# MRCS-BB-Wemos.net
KiCad netlist of a schematic drawn in EAGLE
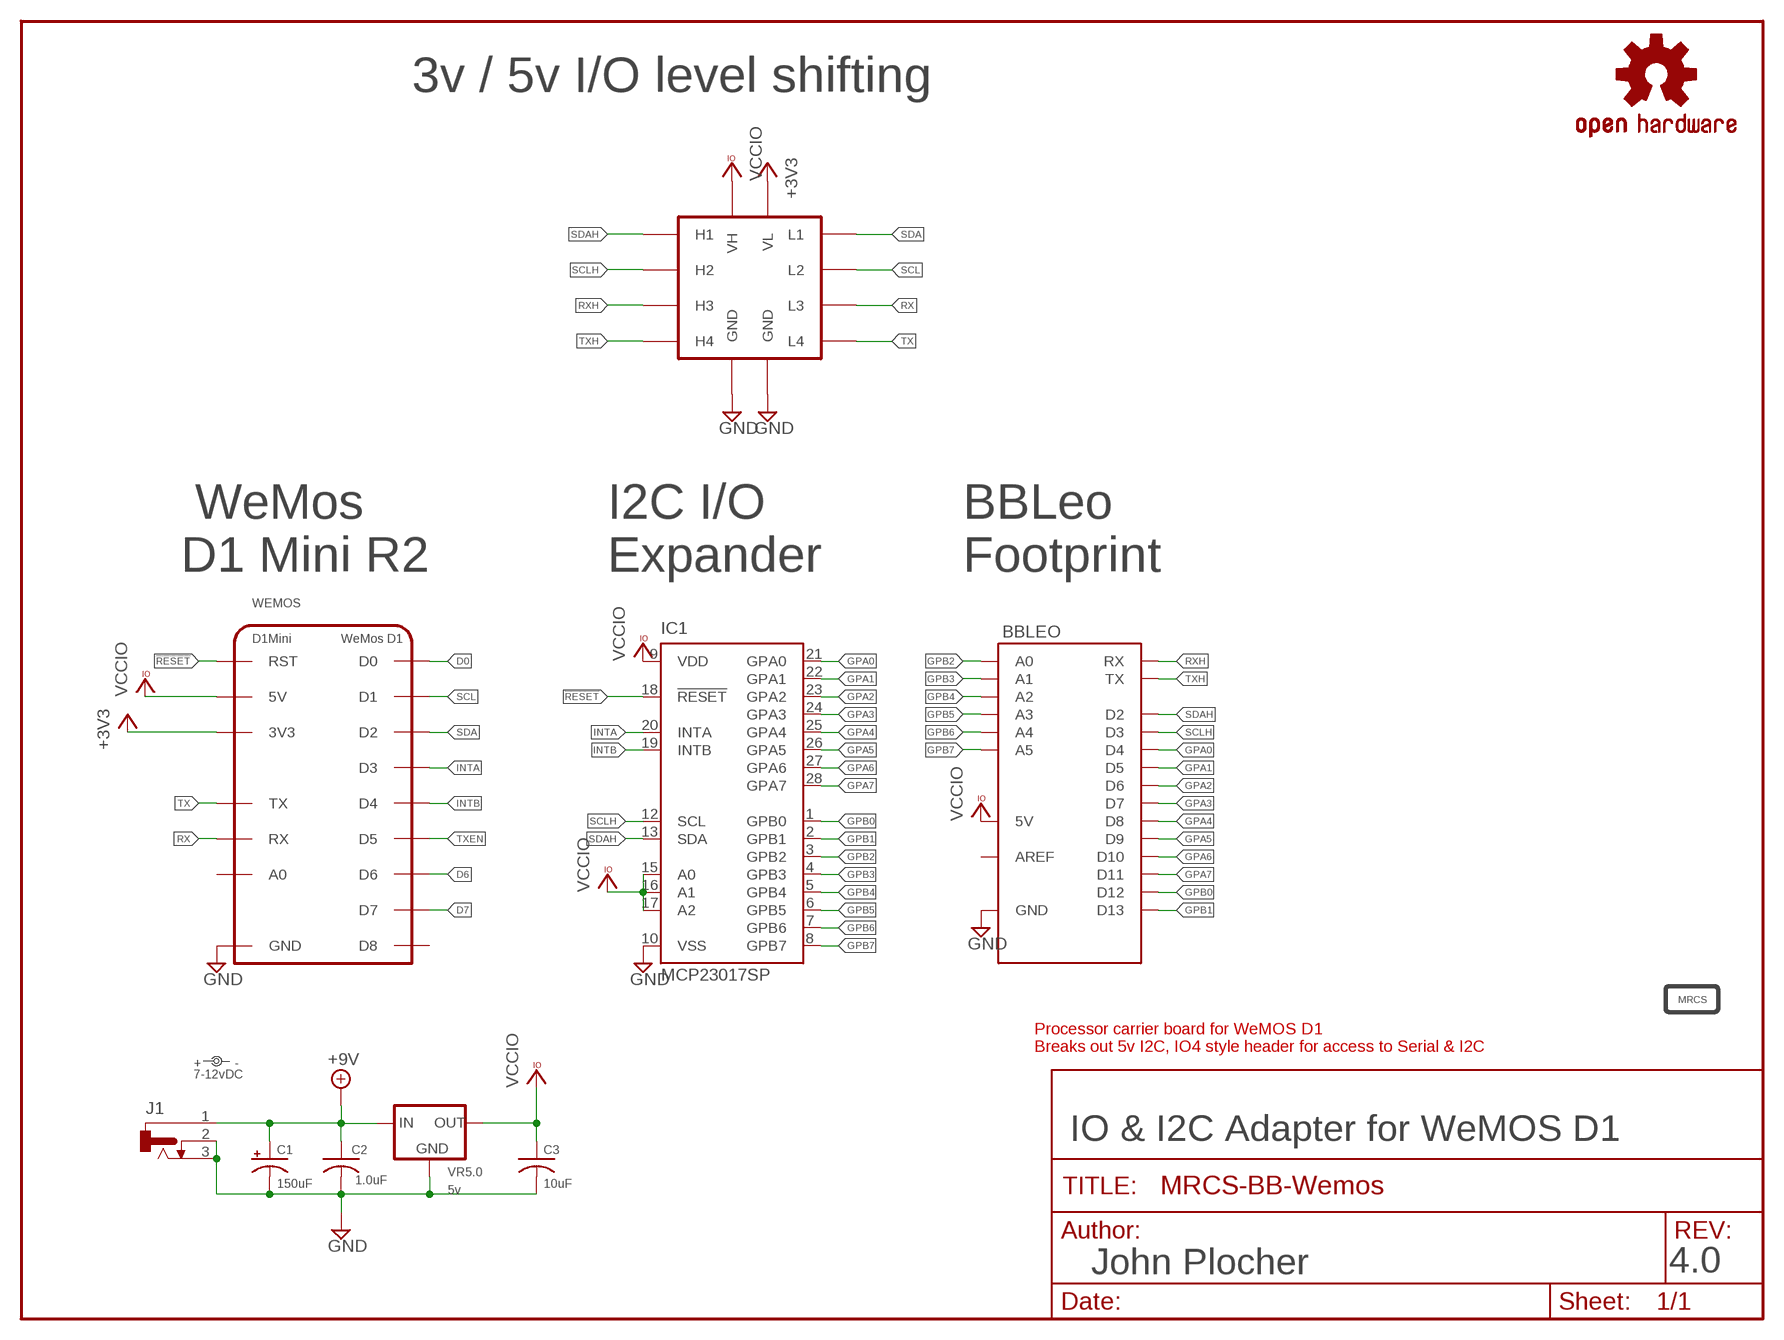
[diagram p0: schematic, sheet 1]

(export (version "E")
  (design (tool "Eeschema 10.0.6"))
  (components
    (comp (ref "BBLEO")
      (value "ARDUINO-BBLEO")
      (footprint "eagle-import:ARDUINO-BBLEO")
      (libsource (lib "eagle-import") (part "ARDUINO-BBLEO"))
    )
    (comp (ref "C1")
      (value "150uF")
      (footprint "eagle-import:E5-10.5")
      (libsource (lib "eagle-import") (part "CAP-POLPTH-5MM"))
    )
    (comp (ref "C2")
      (value "1.0uF")
      (footprint "eagle-import:C050-024X044")
      (libsource (lib "eagle-import") (part "CAPPTH1"))
    )
    (comp (ref "C3")
      (value "10uF")
      (footprint "eagle-import:C050-024X044")
      (libsource (lib "eagle-import") (part "CAPPTH1"))
    )
    (comp (ref "IC1")
      (value "MCP23017SP")
      (footprint "eagle-import:DIL28-3")
      (fields (field (name "MF") "MICROCHIP") (field (name "MPN") "MCP23017-E/SP"))
      (libsource (lib "eagle-import") (part "MCP23017SP"))
    )
    (comp (ref "J1")
      (value "CONNECTOR-DC-POWER-RA")
      (footprint "eagle-import:DCJ0202")
      (libsource (lib "eagle-import") (part "CONNECTOR-DC-POWER-RA"))
    )
    (comp (ref "LABEL1")
      (value "7-12vDC")
      (footprint "eagle-import:PWR_LABEL")
      (libsource (lib "eagle-import") (part "DOC-POWER_LABEL"))
    )
    (comp (ref "LS2")
      (value "I2C-LEVELSHIFTER")
      (footprint "eagle-import:MODULE")
      (libsource (lib "eagle-import") (part "I2C-LEVELSHIFTER"))
    )
    (comp (ref "OSHW1")
      (value "DOC-OSHW-LOGO-L")
      (footprint "eagle-import:OSHW-LOGO-L")
      (libsource (lib "eagle-import") (part "DOC-OSHW-LOGO-L"))
    )
    (comp (ref "U$1")
      (value "DOC-MRCS-LOGOTOP")
      (footprint "eagle-import:MRCS-LOGO")
      (libsource (lib "eagle-import") (part "DOC-MRCS-LOGOTOP"))
    )
    (comp (ref "VR5.0")
      (value "5v")
      (footprint "eagle-import:TO-220-RA")
      (libsource (lib "eagle-import") (part "VREG-?-PTH-RA"))
    )
    (comp (ref "WEMOS")
      (value "D1Mini")
      (footprint "eagle-import:WEMOS-D1")
      (libsource (lib "eagle-import") (part "WEMOS-D1V1"))
    )
  )
  (nets
    (net (code "1") (name "+3V3") (class "Default")
      (node (ref "LS2") (pin "LV") (pinfunction "VL_LV") (pintype "bidirectional"))
      (node (ref "WEMOS") (pin "3V3") (pinfunction "3V3_3V3") (pintype "bidirectional"))
    )
    (net (code "2") (name "+9V") (class "Default")
      (node (ref "C1") (pin "+") (pinfunction "+_+") (pintype "passive"))
      (node (ref "C2") (pin "1") (pinfunction "1_1") (pintype "passive"))
      (node (ref "J1") (pin "1") (pinfunction "1_1") (pintype "passive"))
      (node (ref "VR5.0") (pin "IN") (pinfunction "IN_IN") (pintype "input"))
    )
    (net (code "3") (name "/~{RESET}") (class "Default")
      (node (ref "IC1") (pin "18") (pinfunction "~{RESET}_18") (pintype "input"))
      (node (ref "WEMOS") (pin "RST") (pinfunction "RST_RST") (pintype "bidirectional"))
    )
    (net (code "4") (name "D0") (class "Default")
      (node (ref "WEMOS") (pin "D0") (pinfunction "D0_D0") (pintype "bidirectional"))
    )
    (net (code "5") (name "D6") (class "Default")
      (node (ref "WEMOS") (pin "D6") (pinfunction "D6_D6") (pintype "bidirectional"))
    )
    (net (code "6") (name "D7") (class "Default")
      (node (ref "WEMOS") (pin "D7") (pinfunction "D7_D7") (pintype "bidirectional"))
    )
    (net (code "7") (name "GND") (class "Default")
      (node (ref "BBLEO") (pin "GND@0") (pinfunction "GND_GND@0") (pintype "bidirectional"))
      (node (ref "BBLEO") (pin "GND@1") (pinfunction "GND_GND@1") (pintype "bidirectional"))
      (node (ref "BBLEO") (pin "GND@2") (pinfunction "GND_GND@2") (pintype "bidirectional"))
      (node (ref "BBLEO") (pin "GND@3") (pinfunction "GND_GND@3") (pintype "bidirectional"))
      (node (ref "BBLEO") (pin "GND@4") (pinfunction "GND_GND@4") (pintype "bidirectional"))
      (node (ref "C1") (pin "-") (pinfunction "-_-") (pintype "passive"))
      (node (ref "C2") (pin "2") (pinfunction "2_2") (pintype "passive"))
      (node (ref "C3") (pin "2") (pinfunction "2_2") (pintype "passive"))
      (node (ref "IC1") (pin "10") (pinfunction "VSS_10") (pintype "power_in"))
      (node (ref "J1") (pin "2") (pinfunction "2_2") (pintype "passive"))
      (node (ref "J1") (pin "3") (pinfunction "3_3") (pintype "passive"))
      (node (ref "LS2") (pin "GND@0") (pinfunction "GND_GND@0") (pintype "bidirectional"))
      (node (ref "LS2") (pin "GND@1") (pinfunction "GND_GND@1") (pintype "bidirectional"))
      (node (ref "VR5.0") (pin "GND") (pinfunction "GND_GND") (pintype "input"))
      (node (ref "WEMOS") (pin "GND") (pinfunction "GND_GND") (pintype "bidirectional"))
    )
    (net (code "8") (name "GPA0") (class "Default")
      (node (ref "BBLEO") (pin "D4") (pinfunction "D4_D4") (pintype "bidirectional"))
      (node (ref "IC1") (pin "21") (pinfunction "GPA0_21") (pintype "bidirectional"))
    )
    (net (code "9") (name "GPA1") (class "Default")
      (node (ref "BBLEO") (pin "D5") (pinfunction "D5_D5") (pintype "bidirectional"))
      (node (ref "IC1") (pin "22") (pinfunction "GPA1_22") (pintype "bidirectional"))
    )
    (net (code "10") (name "GPA2") (class "Default")
      (node (ref "BBLEO") (pin "D6") (pinfunction "D6_D6") (pintype "bidirectional"))
      (node (ref "IC1") (pin "23") (pinfunction "GPA2_23") (pintype "bidirectional"))
    )
    (net (code "11") (name "GPA3") (class "Default")
      (node (ref "BBLEO") (pin "D7") (pinfunction "D7_D7") (pintype "bidirectional"))
      (node (ref "IC1") (pin "24") (pinfunction "GPA3_24") (pintype "bidirectional"))
    )
    (net (code "12") (name "GPA4") (class "Default")
      (node (ref "BBLEO") (pin "D8") (pinfunction "D8_D8") (pintype "bidirectional"))
      (node (ref "IC1") (pin "25") (pinfunction "GPA4_25") (pintype "bidirectional"))
    )
    (net (code "13") (name "GPA5") (class "Default")
      (node (ref "BBLEO") (pin "D9") (pinfunction "D9_D9") (pintype "bidirectional"))
      (node (ref "IC1") (pin "26") (pinfunction "GPA5_26") (pintype "bidirectional"))
    )
    (net (code "14") (name "GPA6") (class "Default")
      (node (ref "BBLEO") (pin "D10") (pinfunction "D10_D10") (pintype "bidirectional"))
      (node (ref "IC1") (pin "27") (pinfunction "GPA6_27") (pintype "bidirectional"))
    )
    (net (code "15") (name "GPA7") (class "Default")
      (node (ref "BBLEO") (pin "D11") (pinfunction "D11_D11") (pintype "bidirectional"))
      (node (ref "IC1") (pin "28") (pinfunction "GPA7_28") (pintype "bidirectional"))
    )
    (net (code "16") (name "GPB0") (class "Default")
      (node (ref "BBLEO") (pin "D12") (pinfunction "D12_D12") (pintype "bidirectional"))
      (node (ref "IC1") (pin "1") (pinfunction "GPB0_1") (pintype "bidirectional"))
    )
    (net (code "17") (name "GPB1") (class "Default")
      (node (ref "BBLEO") (pin "D13") (pinfunction "D13_D13") (pintype "bidirectional"))
      (node (ref "IC1") (pin "2") (pinfunction "GPB1_2") (pintype "bidirectional"))
    )
    (net (code "18") (name "GPB2") (class "Default")
      (node (ref "BBLEO") (pin "A0") (pinfunction "A0_A0") (pintype "bidirectional"))
      (node (ref "IC1") (pin "3") (pinfunction "GPB2_3") (pintype "bidirectional"))
    )
    (net (code "19") (name "GPB3") (class "Default")
      (node (ref "BBLEO") (pin "A1") (pinfunction "A1_A1") (pintype "bidirectional"))
      (node (ref "IC1") (pin "4") (pinfunction "GPB3_4") (pintype "bidirectional"))
    )
    (net (code "20") (name "GPB4") (class "Default")
      (node (ref "BBLEO") (pin "A2") (pinfunction "A2_A2") (pintype "bidirectional"))
      (node (ref "IC1") (pin "5") (pinfunction "GPB4_5") (pintype "bidirectional"))
    )
    (net (code "21") (name "GPB5") (class "Default")
      (node (ref "BBLEO") (pin "A3") (pinfunction "A3_A3") (pintype "bidirectional"))
      (node (ref "IC1") (pin "6") (pinfunction "GPB5_6") (pintype "bidirectional"))
    )
    (net (code "22") (name "GPB6") (class "Default")
      (node (ref "BBLEO") (pin "A4") (pinfunction "A4_A4") (pintype "bidirectional"))
      (node (ref "IC1") (pin "7") (pinfunction "GPB6_7") (pintype "bidirectional"))
    )
    (net (code "23") (name "GPB7") (class "Default")
      (node (ref "BBLEO") (pin "A5") (pinfunction "A5_A5") (pintype "bidirectional"))
      (node (ref "IC1") (pin "8") (pinfunction "GPB7_8") (pintype "bidirectional"))
    )
    (net (code "24") (name "INTA") (class "Default")
      (node (ref "IC1") (pin "20") (pinfunction "INTA_20") (pintype "output"))
      (node (ref "WEMOS") (pin "D3") (pinfunction "D3_D3") (pintype "bidirectional"))
    )
    (net (code "25") (name "INTB") (class "Default")
      (node (ref "IC1") (pin "19") (pinfunction "INTB_19") (pintype "output"))
      (node (ref "WEMOS") (pin "D4") (pinfunction "D4_D4") (pintype "bidirectional"))
    )
    (net (code "26") (name "RX") (class "Default")
      (node (ref "LS2") (pin "L3") (pinfunction "L3_L3") (pintype "bidirectional"))
      (node (ref "WEMOS") (pin "RX") (pinfunction "RX_RX") (pintype "bidirectional"))
    )
    (net (code "27") (name "RXH") (class "Default")
      (node (ref "BBLEO") (pin "RX") (pinfunction "RX_RX") (pintype "bidirectional"))
      (node (ref "LS2") (pin "H3") (pinfunction "H3_H3") (pintype "bidirectional"))
    )
    (net (code "28") (name "SCL") (class "Default")
      (node (ref "LS2") (pin "L2") (pinfunction "L2_L2") (pintype "bidirectional"))
      (node (ref "WEMOS") (pin "D1") (pinfunction "D1_D1") (pintype "bidirectional"))
    )
    (net (code "29") (name "SCLH") (class "Default")
      (node (ref "BBLEO") (pin "SCL") (pinfunction "D3_SCL") (pintype "bidirectional"))
      (node (ref "IC1") (pin "12") (pinfunction "SCL_12") (pintype "input"))
      (node (ref "LS2") (pin "H2") (pinfunction "H2_H2") (pintype "bidirectional"))
    )
    (net (code "30") (name "SDA") (class "Default")
      (node (ref "LS2") (pin "L1") (pinfunction "L1_L1") (pintype "bidirectional"))
      (node (ref "WEMOS") (pin "D2") (pinfunction "D2_D2") (pintype "bidirectional"))
    )
    (net (code "31") (name "SDAH") (class "Default")
      (node (ref "BBLEO") (pin "SDA") (pinfunction "D2_SDA") (pintype "bidirectional"))
      (node (ref "IC1") (pin "13") (pinfunction "SDA_13") (pintype "bidirectional"))
      (node (ref "LS2") (pin "H1") (pinfunction "H1_H1") (pintype "bidirectional"))
    )
    (net (code "32") (name "TX") (class "Default")
      (node (ref "LS2") (pin "L4") (pinfunction "L4_L4") (pintype "bidirectional"))
      (node (ref "WEMOS") (pin "TX") (pinfunction "TX_TX") (pintype "bidirectional"))
    )
    (net (code "33") (name "TXEN") (class "Default")
      (node (ref "WEMOS") (pin "D5") (pinfunction "D5_D5") (pintype "bidirectional"))
    )
    (net (code "34") (name "TXH") (class "Default")
      (node (ref "BBLEO") (pin "TX") (pinfunction "TX_TX") (pintype "bidirectional"))
      (node (ref "LS2") (pin "H4") (pinfunction "H4_H4") (pintype "bidirectional"))
    )
    (net (code "35") (name "VCCIO") (class "Default")
      (node (ref "BBLEO") (pin "+5V@1") (pinfunction "5V_+5V@1") (pintype "bidirectional"))
      (node (ref "BBLEO") (pin "+5V@2") (pinfunction "5V_+5V@2") (pintype "bidirectional"))
      (node (ref "BBLEO") (pin "+5V@3") (pinfunction "5V_+5V@3") (pintype "bidirectional"))
      (node (ref "BBLEO") (pin "+5V@4") (pinfunction "5V_+5V@4") (pintype "bidirectional"))
      (node (ref "C3") (pin "1") (pinfunction "1_1") (pintype "passive"))
      (node (ref "IC1") (pin "15") (pinfunction "A0_15") (pintype "input"))
      (node (ref "IC1") (pin "16") (pinfunction "A1_16") (pintype "input"))
      (node (ref "IC1") (pin "17") (pinfunction "A2_17") (pintype "input"))
      (node (ref "IC1") (pin "9") (pinfunction "VDD_9") (pintype "power_in"))
      (node (ref "LS2") (pin "HV") (pinfunction "VH_HV") (pintype "bidirectional"))
      (node (ref "VR5.0") (pin "OUT") (pinfunction "OUT_OUT") (pintype "output"))
      (node (ref "WEMOS") (pin "5V") (pinfunction "5V_5V") (pintype "bidirectional"))
    )
    (net (code "36") (name "unconnected-(BBLEO-AREF-PadAR)") (class "Default")
      (node (ref "BBLEO") (pin "AR") (pinfunction "AREF_AR") (pintype "bidirectional"))
    )
    (net (code "37") (name "unconnected-(WEMOS-PadA0)") (class "Default")
      (node (ref "WEMOS") (pin "A0") (pinfunction "A0_A0") (pintype "bidirectional"))
    )
    (net (code "38") (name "unconnected-(WEMOS-PadD8)") (class "Default")
      (node (ref "WEMOS") (pin "D8") (pinfunction "D8_D8") (pintype "bidirectional"))
    )
  )
)
